# LeftEar.net
KiCad netlist of a schematic drawn in Altium Designer
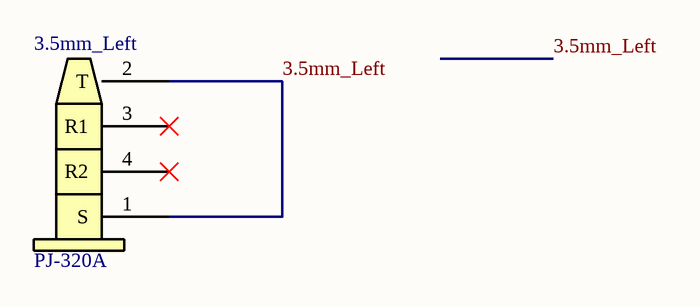
[diagram p0: LeftEar.SchDoc]

(export (version "E")
  (design (tool "Eeschema 10.0.6"))
  (components
    (comp (ref "3.5mm_Left")
      (value "PJ-320A")
      (footprint "PCBComponent_1")
      (description "A thru hole 3.5mm TRRS audio jack connector")
      (libsource (lib "PJ-320A-New") (part "PJ-320A"))
    )
  )
  (nets
    (net (code "1") (name "/3.5mm_Left") (class "Default")
      (node (ref "3.5mm_Left") (pin "1") (pinfunction "S_1") (pintype "passive"))
      (node (ref "3.5mm_Left") (pin "2") (pinfunction "T_2") (pintype "passive"))
    )
    (net (code "2") (name "unconnected-(3.5mm_Left-R1-Pad3)") (class "Default")
      (node (ref "3.5mm_Left") (pin "3") (pinfunction "R1_3") (pintype "passive+no_connect"))
    )
    (net (code "3") (name "unconnected-(3.5mm_Left-R2-Pad4)") (class "Default")
      (node (ref "3.5mm_Left") (pin "4") (pinfunction "R2_4") (pintype "passive+no_connect"))
    )
  )
)
